# IMUinator2368_v2.net
KiCad netlist of a schematic drawn in EAGLE
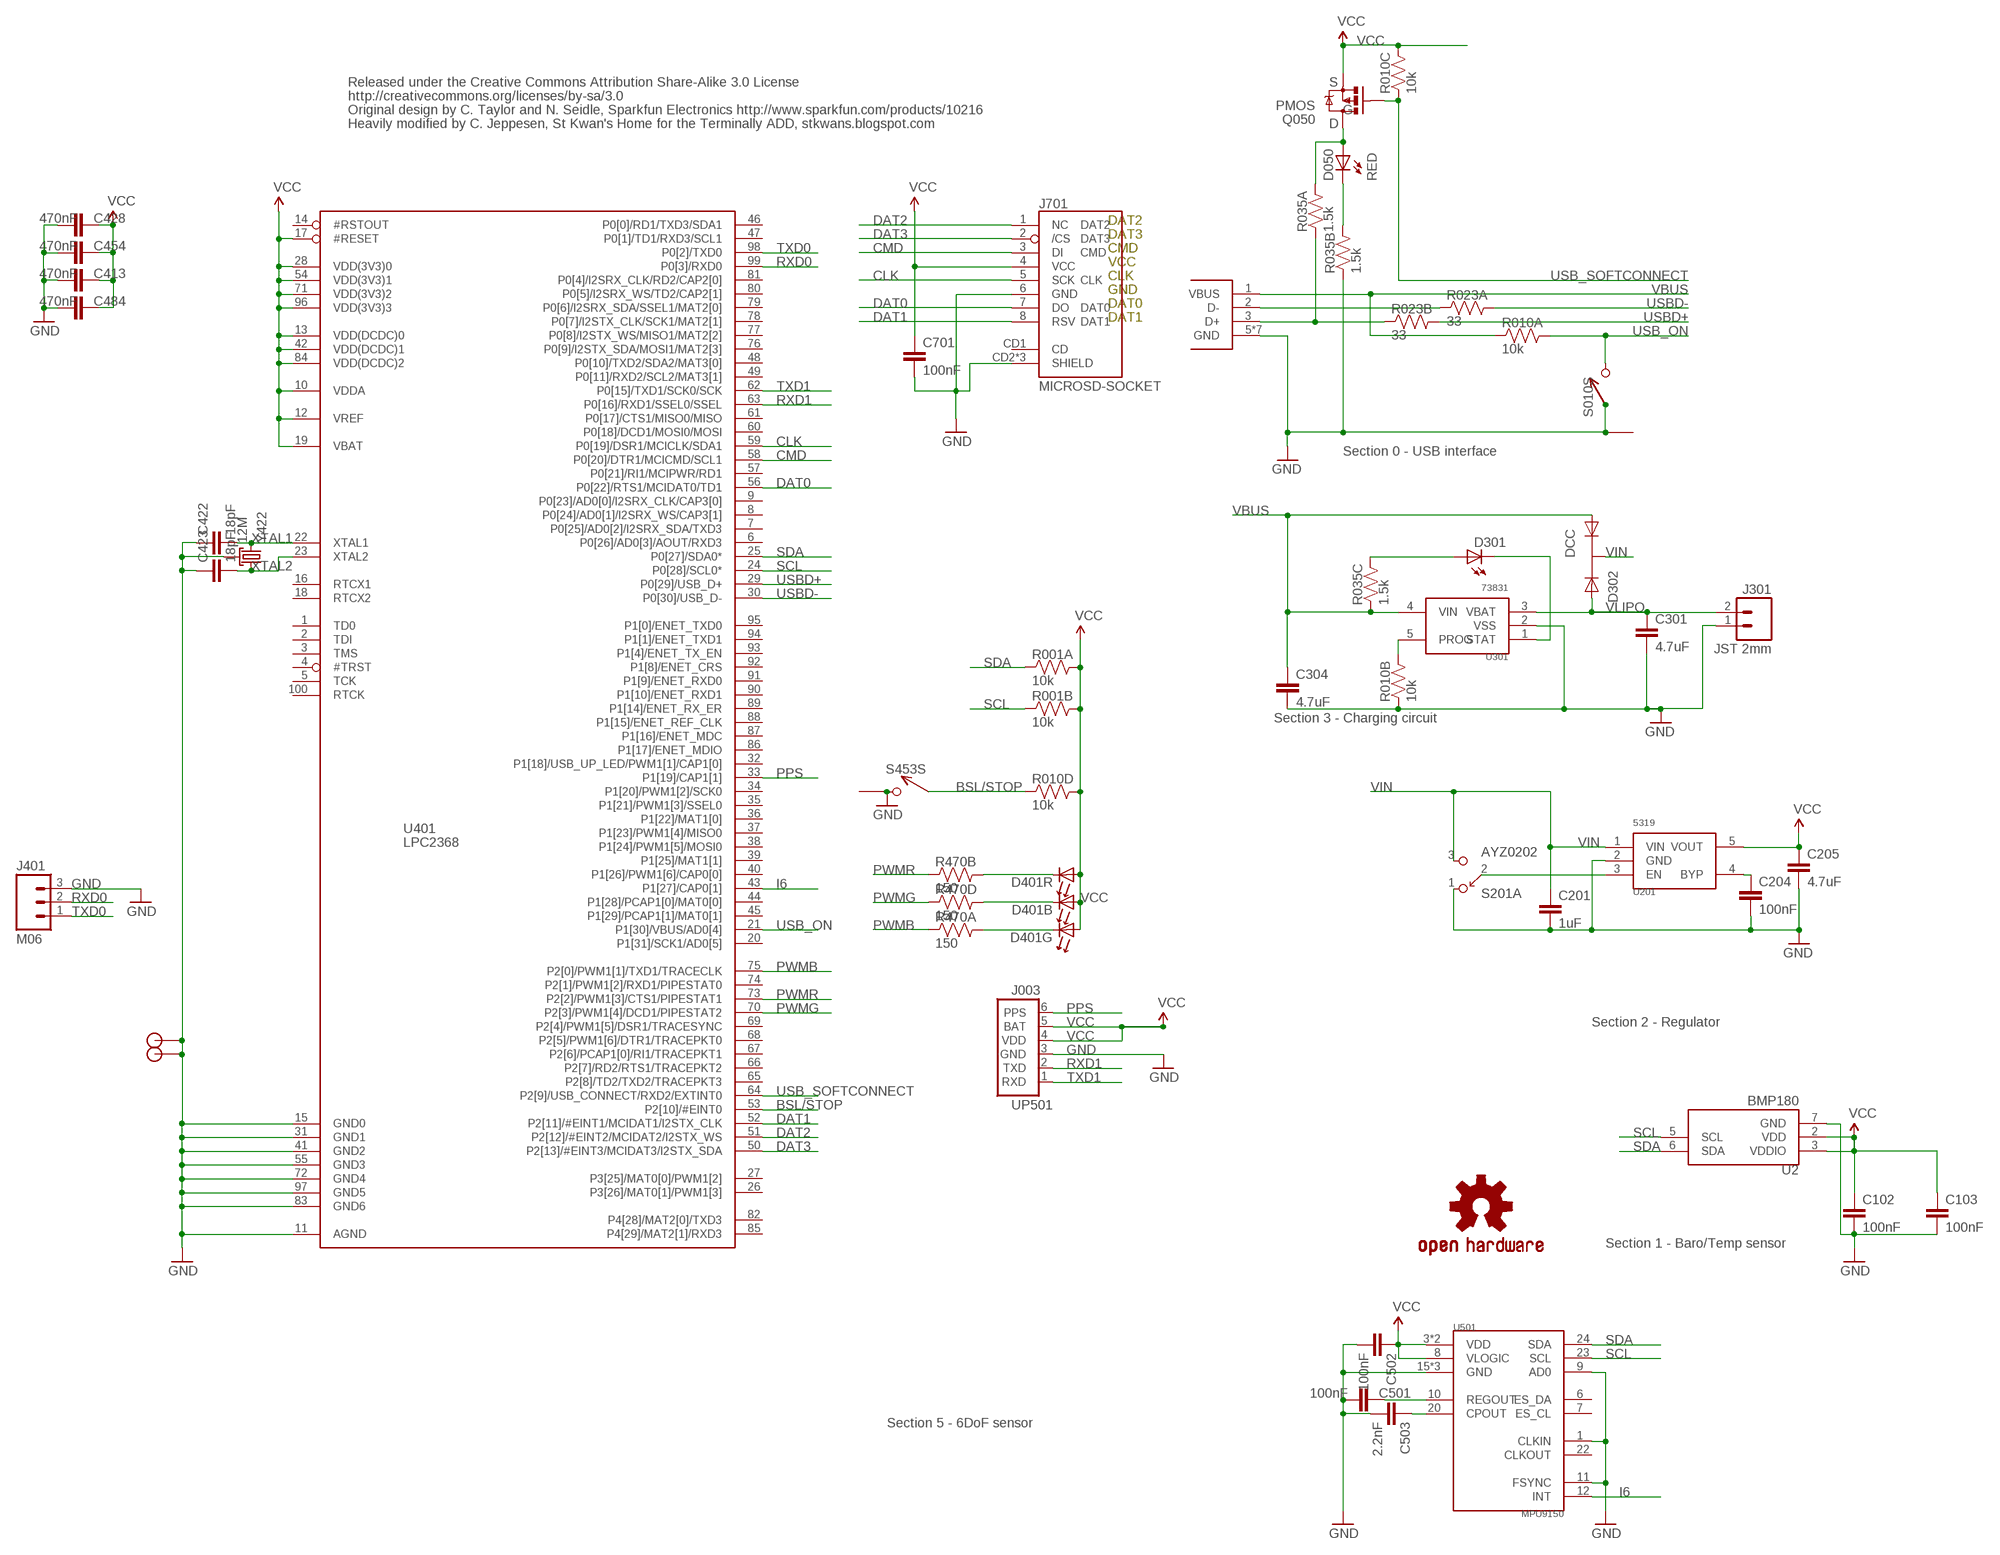
[diagram p0: schematic, sheet 1]

(export (version "E")
  (design (tool "Eeschema 10.0.6"))
  (components
    (comp (ref "C102")
      (value "100nF")
      (footprint "eagle-import:0402-CAP")
      (libsource (lib "eagle-import") (part "CAP0402-CAP"))
    )
    (comp (ref "C103")
      (value "100nF")
      (footprint "eagle-import:0402-CAP")
      (libsource (lib "eagle-import") (part "CAP0402-CAP"))
    )
    (comp (ref "C201")
      (value "1uF")
      (footprint "eagle-import:0402-CAP")
      (libsource (lib "eagle-import") (part "CAP0402-CAP"))
    )
    (comp (ref "C204")
      (value "100nF")
      (footprint "eagle-import:0402-CAP")
      (libsource (lib "eagle-import") (part "CAP0402-CAP"))
    )
    (comp (ref "C205")
      (value "4.7uF")
      (footprint "eagle-import:0402-CAP")
      (libsource (lib "eagle-import") (part "CAP0402-CAP"))
    )
    (comp (ref "C301")
      (value "4.7uF")
      (footprint "eagle-import:0402-CAP")
      (libsource (lib "eagle-import") (part "CAP0402-CAP"))
    )
    (comp (ref "C304")
      (value "4.7uF")
      (footprint "eagle-import:0402-CAP")
      (libsource (lib "eagle-import") (part "CAP0402-CAP"))
    )
    (comp (ref "C413")
      (value "470nF")
      (footprint "eagle-import:0402-CAP")
      (libsource (lib "eagle-import") (part "CAP0402-CAP"))
    )
    (comp (ref "C422")
      (value "18pF")
      (footprint "eagle-import:0402-CAP")
      (libsource (lib "eagle-import") (part "CAP0402-CAP"))
    )
    (comp (ref "C423")
      (value "18pF")
      (footprint "eagle-import:0402-CAP")
      (libsource (lib "eagle-import") (part "CAP0402-CAP"))
    )
    (comp (ref "C428")
      (value "470nF")
      (footprint "eagle-import:0402-CAP")
      (libsource (lib "eagle-import") (part "CAP0402-CAP"))
    )
    (comp (ref "C454")
      (value "470nF")
      (footprint "eagle-import:0402-CAP")
      (libsource (lib "eagle-import") (part "CAP0402-CAP"))
    )
    (comp (ref "C484")
      (value "470nF")
      (footprint "eagle-import:0402-CAP")
      (libsource (lib "eagle-import") (part "CAP0402-CAP"))
    )
    (comp (ref "C501")
      (value "100nF")
      (footprint "eagle-import:0402-CAP")
      (libsource (lib "eagle-import") (part "CAP0402-CAP"))
    )
    (comp (ref "C502")
      (value "100nF")
      (footprint "eagle-import:0402-CAP")
      (libsource (lib "eagle-import") (part "CAP0402-CAP"))
    )
    (comp (ref "C503")
      (value "2.2nF")
      (footprint "eagle-import:0402-CAP")
      (libsource (lib "eagle-import") (part "CAP0402-CAP"))
    )
    (comp (ref "C701")
      (value "100nF")
      (footprint "eagle-import:0402-CAP")
      (libsource (lib "eagle-import") (part "CAP0402-CAP"))
    )
    (comp (ref "D050")
      (value "RED")
      (footprint "eagle-import:LED-0603")
      (libsource (lib "eagle-import") (part "LED0603"))
    )
    (comp (ref "D301")
      (value "RED")
      (footprint "eagle-import:LED-0603")
      (libsource (lib "eagle-import") (part "LED0603"))
    )
    (comp (ref "D302")
      (value "DCC")
      (footprint "eagle-import:SOT-23-3")
      (libsource (lib "eagle-import") (part "PMEG2005CT"))
    )
    (comp (ref "D401")
      (value "SMLP36RGB2W(R)")
      (footprint "eagle-import:SMLP36")
      (libsource (lib "eagle-import") (part "SMLP36RGB2W(R)"))
    )
    (comp (ref "J001")
      (value "USB_MICROB_JSTGCT")
      (footprint "eagle-import:USB_MICROB_3075")
      (libsource (lib "eagle-import") (part "USB_MICROB_JSTGCT"))
    )
    (comp (ref "J003")
      (value "UP501")
      (footprint "eagle-import:UP501")
      (libsource (lib "eagle-import") (part "UP501"))
    )
    (comp (ref "J301")
      (value "JST 2mm")
      (footprint "eagle-import:JST-2-SMD")
      (libsource (lib "eagle-import") (part "M02-JST-2MM-SMT"))
    )
    (comp (ref "J401")
      (value "M06")
      (footprint "eagle-import:1X03")
      (libsource (lib "eagle-import") (part "M03PTH"))
    )
    (comp (ref "J701")
      (value "MICROSD-SOCKET")
      (footprint "eagle-import:MICROSD-SOCKET-PP")
      (libsource (lib "eagle-import") (part "MICROSD-SOCKET"))
    )
    (comp (ref "JP1")
      (value "STANDOFF")
      (footprint "eagle-import:STANDOFF")
      (libsource (lib "eagle-import") (part "STANDOFF"))
    )
    (comp (ref "JP2")
      (value "STANDOFF")
      (footprint "eagle-import:STANDOFF")
      (libsource (lib "eagle-import") (part "STANDOFF"))
    )
    (comp (ref "Q050")
      (value "PMOS")
      (footprint "eagle-import:SOT23-3")
      (libsource (lib "eagle-import") (part "MOSFET-PCHANNELSMD"))
    )
    (comp (ref "R001")
      (value "10k")
      (footprint "eagle-import:CRA02")
      (libsource (lib "eagle-import") (part "RP2EXB24V"))
    )
    (comp (ref "R010")
      (value "10k")
      (footprint "eagle-import:CRA04")
      (libsource (lib "eagle-import") (part "RP404"))
    )
    (comp (ref "R023")
      (value "33")
      (footprint "eagle-import:CRA02")
      (libsource (lib "eagle-import") (part "RP2EXB24V"))
    )
    (comp (ref "R035")
      (value "1.5k")
      (footprint "eagle-import:CRA04")
      (libsource (lib "eagle-import") (part "RP404"))
    )
    (comp (ref "R470")
      (value "150")
      (footprint "eagle-import:CRA04")
      (libsource (lib "eagle-import") (part "RP404"))
    )
    (comp (ref "S010")
      (value "SPST")
      (footprint "eagle-import:B3U-1100P")
      (fields (field (name "DIGIKEY") "SW1021CT-ND"))
      (libsource (lib "eagle-import") (part "B3U-1100P"))
    )
    (comp (ref "S201")
      (value "AYZ0202")
      (footprint "eagle-import:AYZ0202")
      (libsource (lib "eagle-import") (part "AYZ0202"))
    )
    (comp (ref "S453")
      (value "SPST")
      (footprint "eagle-import:B3U-1100P")
      (fields (field (name "DIGIKEY") "SW1021CT-ND"))
      (libsource (lib "eagle-import") (part "B3U-1100P"))
    )
    (comp (ref "U$3")
      (value "OSHW-LOGOS")
      (footprint "eagle-import:OSHW-LOGO-S")
      (libsource (lib "eagle-import") (part "OSHW-LOGOS"))
    )
    (comp (ref "U2")
      (value "BMP180")
      (footprint "eagle-import:BMP180")
      (libsource (lib "eagle-import") (part "BMP180"))
    )
    (comp (ref "U201")
      (value "5319")
      (footprint "eagle-import:SOT-23-5")
      (libsource (lib "eagle-import") (part "MIC5319D5"))
    )
    (comp (ref "U301")
      (value "73831")
      (footprint "eagle-import:SOT-23-5")
      (libsource (lib "eagle-import") (part "MCP73831"))
    )
    (comp (ref "U401")
      (value "LPC2368")
      (footprint "eagle-import:LQFP100")
      (libsource (lib "eagle-import") (part "LPC2368"))
    )
    (comp (ref "U501")
      (value "MPU9150")
      (footprint "eagle-import:LLGA24")
      (libsource (lib "eagle-import") (part "MPU9150"))
    )
    (comp (ref "Y422")
      (value "12M")
      (footprint "eagle-import:CRYSTAL_SMD_2MM_2_5MM")
      (fields (field (name "DIGIKEY") "887-1316-1-ND"))
      (libsource (lib "eagle-import") (part "CX2520"))
    )
  )
  (nets
    (net (code "1") (name "/BSL{slash}STOP") (class "Default")
      (node (ref "R010") (pin "4") (pinfunction "1_4") (pintype "passive"))
      (node (ref "S453") (pin "P$1") (pinfunction "1_P$1") (pintype "bidirectional"))
      (node (ref "U401") (pin "53") (pinfunction "P2[10]/#EINT0_53") (pintype "bidirectional"))
    )
    (net (code "2") (name "/CLK") (class "Default")
      (node (ref "J701") (pin "5") (pinfunction "SCK_5") (pintype "bidirectional"))
      (node (ref "U401") (pin "59") (pinfunction "P0[19]/DSR1/MCICLK/SDA1_59") (pintype "bidirectional"))
    )
    (net (code "3") (name "/CMD") (class "Default")
      (node (ref "J701") (pin "3") (pinfunction "DI_3") (pintype "bidirectional"))
      (node (ref "U401") (pin "58") (pinfunction "P0[20]/DTR1/MCICMD/SCL1_58") (pintype "bidirectional"))
    )
    (net (code "4") (name "/DAT0") (class "Default")
      (node (ref "J701") (pin "7") (pinfunction "DO_7") (pintype "bidirectional"))
      (node (ref "U401") (pin "56") (pinfunction "P0[22]/RTS1/MCIDAT0/TD1_56") (pintype "bidirectional"))
    )
    (net (code "5") (name "/DAT1") (class "Default")
      (node (ref "J701") (pin "8") (pinfunction "RSV_8") (pintype "bidirectional"))
      (node (ref "U401") (pin "52") (pinfunction "P2[11]/#EINT1/MCIDAT1/I2STX_CLK_52") (pintype "bidirectional"))
    )
    (net (code "6") (name "/DAT2") (class "Default")
      (node (ref "J701") (pin "1") (pinfunction "NC_1") (pintype "bidirectional"))
      (node (ref "U401") (pin "51") (pinfunction "P2[12]/#EINT2/MCIDAT2/I2STX_WS_51") (pintype "bidirectional"))
    )
    (net (code "7") (name "/DAT3") (class "Default")
      (node (ref "J701") (pin "2") (pinfunction "/CS_2") (pintype "bidirectional"))
      (node (ref "U401") (pin "50") (pinfunction "P2[13]/#EINT3/MCIDAT3/I2STX_SDA_50") (pintype "bidirectional"))
    )
    (net (code "8") (name "/I6") (class "Default")
      (node (ref "U401") (pin "43") (pinfunction "P1[27]/CAP0[1]_43") (pintype "bidirectional"))
      (node (ref "U501") (pin "12") (pinfunction "INT_12") (pintype "bidirectional"))
    )
    (net (code "9") (name "/PPS") (class "Default")
      (node (ref "J003") (pin "6") (pinfunction "PPS_6") (pintype "passive"))
      (node (ref "U401") (pin "33") (pinfunction "P1[19]/CAP1[1]_33") (pintype "bidirectional"))
    )
    (net (code "10") (name "/PWMB") (class "Default")
      (node (ref "R470") (pin "1") (pinfunction "1_1") (pintype "passive"))
      (node (ref "U401") (pin "75") (pinfunction "P2[0]/PWM1[1]/TXD1/TRACECLK_75") (pintype "bidirectional"))
    )
    (net (code "11") (name "/PWMG") (class "Default")
      (node (ref "R470") (pin "4") (pinfunction "1_4") (pintype "passive"))
      (node (ref "U401") (pin "70") (pinfunction "P2[3]/PWM1[4]/DCD1/PIPESTAT2_70") (pintype "bidirectional"))
    )
    (net (code "12") (name "/PWMR") (class "Default")
      (node (ref "R470") (pin "2") (pinfunction "1_2") (pintype "passive"))
      (node (ref "U401") (pin "73") (pinfunction "P2[2]/PWM1[3]/CTS1/PIPESTAT1_73") (pintype "bidirectional"))
    )
    (net (code "13") (name "/RXD0") (class "Default")
      (node (ref "J401") (pin "2") (pinfunction "2_2") (pintype "passive"))
      (node (ref "U401") (pin "99") (pinfunction "P0[3]/RXD0_99") (pintype "bidirectional"))
    )
    (net (code "14") (name "/RXD1") (class "Default")
      (node (ref "J003") (pin "2") (pinfunction "TXD_2") (pintype "passive"))
      (node (ref "U401") (pin "63") (pinfunction "P0[16]/RXD1/SSEL0/SSEL_63") (pintype "bidirectional"))
    )
    (net (code "15") (name "/SCL") (class "Default")
      (node (ref "R001") (pin "2") (pinfunction "1_2") (pintype "passive"))
      (node (ref "U2") (pin "5") (pinfunction "SCL_5") (pintype "input"))
      (node (ref "U401") (pin "24") (pinfunction "P0[28]/SCL0*_24") (pintype "bidirectional"))
      (node (ref "U501") (pin "23") (pinfunction "SCL_23") (pintype "bidirectional"))
    )
    (net (code "16") (name "/SDA") (class "Default")
      (node (ref "R001") (pin "1") (pinfunction "1_1") (pintype "passive"))
      (node (ref "U2") (pin "6") (pinfunction "SDA_6") (pintype "bidirectional"))
      (node (ref "U401") (pin "25") (pinfunction "P0[27]/SDA0*_25") (pintype "bidirectional"))
      (node (ref "U501") (pin "24") (pinfunction "SDA_24") (pintype "bidirectional"))
    )
    (net (code "17") (name "/TXD0") (class "Default")
      (node (ref "J401") (pin "1") (pinfunction "1_1") (pintype "passive"))
      (node (ref "U401") (pin "98") (pinfunction "P0[2]/TXD0_98") (pintype "bidirectional"))
    )
    (net (code "18") (name "/TXD1") (class "Default")
      (node (ref "J003") (pin "1") (pinfunction "RXD_1") (pintype "passive"))
      (node (ref "U401") (pin "62") (pinfunction "P0[15]/TXD1/SCK0/SCK_62") (pintype "bidirectional"))
    )
    (net (code "19") (name "/USBD+") (class "Default")
      (node (ref "R023") (pin "3") (pinfunction "2_3") (pintype "passive"))
      (node (ref "U401") (pin "29") (pinfunction "P0[29]/USB_D+_29") (pintype "bidirectional"))
    )
    (net (code "20") (name "/USBD-") (class "Default")
      (node (ref "R023") (pin "4") (pinfunction "2_4") (pintype "passive"))
      (node (ref "U401") (pin "30") (pinfunction "P0[30]/USB_D-_30") (pintype "bidirectional"))
    )
    (net (code "21") (name "/USB_ON") (class "Default")
      (node (ref "R010") (pin "8") (pinfunction "2_8") (pintype "passive"))
      (node (ref "S010") (pin "P$2") (pinfunction "2_P$2") (pintype "bidirectional"))
      (node (ref "U401") (pin "21") (pinfunction "P1[30]/VBUS/AD0[4]_21") (pintype "bidirectional"))
    )
    (net (code "22") (name "/USB_SOFTCONNECT") (class "Default")
      (node (ref "Q050") (pin "1") (pinfunction "G_1") (pintype "passive"))
      (node (ref "R010") (pin "3") (pinfunction "1_3") (pintype "passive"))
      (node (ref "U401") (pin "64") (pinfunction "P2[9]/USB_CONNECT/RXD2/EXTINT0_64") (pintype "bidirectional"))
    )
    (net (code "23") (name "/VBUS") (class "Default")
      (node (ref "C304") (pin "1") (pinfunction "1_1") (pintype "passive"))
      (node (ref "D302") (pin "1") (pinfunction "A1_1") (pintype "passive"))
      (node (ref "J001") (pin "1") (pinfunction "VBUS_1") (pintype "bidirectional"))
      (node (ref "R010") (pin "1") (pinfunction "1_1") (pintype "passive"))
      (node (ref "R035") (pin "3") (pinfunction "1_3") (pintype "passive"))
      (node (ref "U301") (pin "4") (pinfunction "VIN_4") (pintype "power_in"))
    )
    (net (code "24") (name "/VIN") (class "Default")
      (node (ref "C201") (pin "1") (pinfunction "1_1") (pintype "passive"))
      (node (ref "D302") (pin "3") (pinfunction "K_3") (pintype "passive"))
      (node (ref "S201") (pin "3") (pinfunction "P$2_3") (pintype "bidirectional"))
      (node (ref "U201") (pin "1") (pinfunction "VIN_1") (pintype "bidirectional"))
    )
    (net (code "25") (name "/VLIPO") (class "Default")
      (node (ref "C301") (pin "1") (pinfunction "1_1") (pintype "passive"))
      (node (ref "D302") (pin "2") (pinfunction "A2_2") (pintype "passive"))
      (node (ref "J301") (pin "2") (pinfunction "2_2") (pintype "passive"))
      (node (ref "U301") (pin "3") (pinfunction "VBAT_3") (pintype "power_in"))
    )
    (net (code "26") (name "/XTAL1") (class "Default")
      (node (ref "C422") (pin "2") (pinfunction "2_2") (pintype "passive"))
      (node (ref "U401") (pin "22") (pinfunction "XTAL1_22") (pintype "bidirectional"))
      (node (ref "Y422") (pin "3") (pinfunction "2_3") (pintype "passive"))
    )
    (net (code "27") (name "/XTAL2") (class "Default")
      (node (ref "C423") (pin "2") (pinfunction "2_2") (pintype "passive"))
      (node (ref "U401") (pin "23") (pinfunction "XTAL2_23") (pintype "bidirectional"))
      (node (ref "Y422") (pin "1") (pinfunction "1_1") (pintype "passive"))
    )
    (net (code "28") (name "GND") (class "Default")
      (node (ref "C102") (pin "2") (pinfunction "2_2") (pintype "passive"))
      (node (ref "C103") (pin "2") (pinfunction "2_2") (pintype "passive"))
      (node (ref "C201") (pin "2") (pinfunction "2_2") (pintype "passive"))
      (node (ref "C204") (pin "2") (pinfunction "2_2") (pintype "passive"))
      (node (ref "C205") (pin "2") (pinfunction "2_2") (pintype "passive"))
      (node (ref "C301") (pin "2") (pinfunction "2_2") (pintype "passive"))
      (node (ref "C304") (pin "2") (pinfunction "2_2") (pintype "passive"))
      (node (ref "C413") (pin "2") (pinfunction "2_2") (pintype "passive"))
      (node (ref "C422") (pin "1") (pinfunction "1_1") (pintype "passive"))
      (node (ref "C423") (pin "1") (pinfunction "1_1") (pintype "passive"))
      (node (ref "C428") (pin "2") (pinfunction "2_2") (pintype "passive"))
      (node (ref "C454") (pin "2") (pinfunction "2_2") (pintype "passive"))
      (node (ref "C484") (pin "2") (pinfunction "2_2") (pintype "passive"))
      (node (ref "C501") (pin "2") (pinfunction "2_2") (pintype "passive"))
      (node (ref "C502") (pin "2") (pinfunction "2_2") (pintype "passive"))
      (node (ref "C503") (pin "2") (pinfunction "2_2") (pintype "passive"))
      (node (ref "C701") (pin "2") (pinfunction "2_2") (pintype "passive"))
      (node (ref "J001") (pin "5") (pinfunction "GND_5") (pintype "bidirectional"))
      (node (ref "J001") (pin "P$1") (pinfunction "GND_P$1") (pintype "bidirectional"))
      (node (ref "J001") (pin "P$10") (pinfunction "GND_P$10") (pintype "bidirectional"))
      (node (ref "J001") (pin "P$2") (pinfunction "GND_P$2") (pintype "bidirectional"))
      (node (ref "J001") (pin "P$3") (pinfunction "GND_P$3") (pintype "bidirectional"))
      (node (ref "J001") (pin "P$4") (pinfunction "GND_P$4") (pintype "bidirectional"))
      (node (ref "J001") (pin "P$8") (pinfunction "GND_P$8") (pintype "bidirectional"))
      (node (ref "J003") (pin "3") (pinfunction "GND_3") (pintype "passive"))
      (node (ref "J301") (pin "1") (pinfunction "1_1") (pintype "passive"))
      (node (ref "J401") (pin "3") (pinfunction "3_3") (pintype "passive"))
      (node (ref "J701") (pin "6") (pinfunction "GND_6") (pintype "bidirectional"))
      (node (ref "J701") (pin "CD2") (pinfunction "SHIELD_CD2") (pintype "bidirectional"))
      (node (ref "J701") (pin "GND1") (pinfunction "SHIELD_GND1") (pintype "bidirectional"))
      (node (ref "J701") (pin "GND3") (pinfunction "SHIELD_GND3") (pintype "bidirectional"))
      (node (ref "JP1") (pin "P$1") (pinfunction "P$1_P$1") (pintype "bidirectional"))
      (node (ref "JP2") (pin "P$1") (pinfunction "P$1_P$1") (pintype "bidirectional"))
      (node (ref "R010") (pin "2") (pinfunction "1_2") (pintype "passive"))
      (node (ref "R035") (pin "2") (pinfunction "1_2") (pintype "passive"))
      (node (ref "S010") (pin "P$1") (pinfunction "1_P$1") (pintype "bidirectional"))
      (node (ref "S010") (pin "P$3") (pinfunction "1_P$3") (pintype "bidirectional"))
      (node (ref "S201") (pin "1") (pinfunction "P$1_1") (pintype "bidirectional"))
      (node (ref "S453") (pin "P$2") (pinfunction "2_P$2") (pintype "bidirectional"))
      (node (ref "S453") (pin "P$3") (pinfunction "1_P$3") (pintype "bidirectional"))
      (node (ref "U2") (pin "7") (pinfunction "GND_7") (pintype "power_in"))
      (node (ref "U201") (pin "2") (pinfunction "GND_2") (pintype "bidirectional"))
      (node (ref "U301") (pin "2") (pinfunction "VSS_2") (pintype "power_in"))
      (node (ref "U401") (pin "11") (pinfunction "AGND_11") (pintype "bidirectional"))
      (node (ref "U401") (pin "15") (pinfunction "GND0_15") (pintype "bidirectional"))
      (node (ref "U401") (pin "31") (pinfunction "GND1_31") (pintype "bidirectional"))
      (node (ref "U401") (pin "41") (pinfunction "GND2_41") (pintype "bidirectional"))
      (node (ref "U401") (pin "55") (pinfunction "GND3_55") (pintype "bidirectional"))
      (node (ref "U401") (pin "72") (pinfunction "GND4_72") (pintype "bidirectional"))
      (node (ref "U401") (pin "83") (pinfunction "GND6_83") (pintype "bidirectional"))
      (node (ref "U401") (pin "97") (pinfunction "GND5_97") (pintype "bidirectional"))
      (node (ref "U501") (pin "1") (pinfunction "CLKIN_1") (pintype "bidirectional"))
      (node (ref "U501") (pin "11") (pinfunction "FSYNC_11") (pintype "bidirectional"))
      (node (ref "U501") (pin "15") (pinfunction "GND_15") (pintype "bidirectional"))
      (node (ref "U501") (pin "17") (pinfunction "GND_17") (pintype "bidirectional"))
      (node (ref "U501") (pin "18") (pinfunction "GND_18") (pintype "bidirectional"))
      (node (ref "U501") (pin "9") (pinfunction "AD0_9") (pintype "bidirectional"))
      (node (ref "Y422") (pin "2") (pinfunction "GND_2") (pintype "passive"))
      (node (ref "Y422") (pin "4") (pinfunction "GND_4") (pintype "passive"))
    )
    (net (code "29") (name "Net-(D401A-C)") (class "Default")
      (node (ref "D401") (pin "1") (pinfunction "C_1") (pintype "passive"))
      (node (ref "R470") (pin "5") (pinfunction "2_5") (pintype "passive"))
    )
    (net (code "30") (name "Net-(D401B-C)") (class "Default")
      (node (ref "D401") (pin "5") (pinfunction "C_5") (pintype "passive"))
      (node (ref "R470") (pin "8") (pinfunction "2_8") (pintype "passive"))
    )
    (net (code "31") (name "Net-(D401C-C)") (class "Default")
      (node (ref "D401") (pin "3") (pinfunction "C_3") (pintype "passive"))
      (node (ref "R470") (pin "7") (pinfunction "2_7") (pintype "passive"))
    )
    (net (code "32") (name "Net-(J001-D+)") (class "Default")
      (node (ref "J001") (pin "3") (pinfunction "D+_3") (pintype "bidirectional"))
      (node (ref "R023") (pin "2") (pinfunction "1_2") (pintype "passive"))
      (node (ref "R035") (pin "1") (pinfunction "1_1") (pintype "passive"))
    )
    (net (code "33") (name "Net-(J001-D-)") (class "Default")
      (node (ref "J001") (pin "2") (pinfunction "D-_2") (pintype "bidirectional"))
      (node (ref "R023") (pin "1") (pinfunction "1_1") (pintype "passive"))
    )
    (net (code "34") (name "Net-(Q050-D)") (class "Default")
      (node (ref "D050") (pin "A") (pinfunction "A_A") (pintype "passive"))
      (node (ref "Q050") (pin "3") (pinfunction "D_3") (pintype "passive"))
      (node (ref "R035") (pin "8") (pinfunction "2_8") (pintype "passive"))
    )
    (net (code "35") (name "Net-(R010B-2)") (class "Default")
      (node (ref "R010") (pin "7") (pinfunction "2_7") (pintype "passive"))
      (node (ref "U301") (pin "5") (pinfunction "PROG_5") (pintype "passive"))
    )
    (net (code "36") (name "Net-(R035B-2)") (class "Default")
      (node (ref "D050") (pin "C") (pinfunction "C_C") (pintype "passive"))
      (node (ref "R035") (pin "7") (pinfunction "2_7") (pintype "passive"))
    )
    (net (code "37") (name "Net-(R035C-2)") (class "Default")
      (node (ref "D301") (pin "A") (pinfunction "A_A") (pintype "passive"))
      (node (ref "R035") (pin "6") (pinfunction "2_6") (pintype "passive"))
    )
    (net (code "38") (name "Net-(S201A-P$3)") (class "Default")
      (node (ref "S201") (pin "2") (pinfunction "P$3_2") (pintype "bidirectional"))
      (node (ref "U201") (pin "3") (pinfunction "EN_3") (pintype "bidirectional"))
    )
    (net (code "39") (name "Net-(U201-BYP)") (class "Default")
      (node (ref "C204") (pin "1") (pinfunction "1_1") (pintype "passive"))
      (node (ref "U201") (pin "4") (pinfunction "BYP_4") (pintype "bidirectional"))
    )
    (net (code "40") (name "Net-(U301-STAT)") (class "Default")
      (node (ref "D301") (pin "C") (pinfunction "C_C") (pintype "passive"))
      (node (ref "U301") (pin "1") (pinfunction "STAT_1") (pintype "bidirectional"))
    )
    (net (code "41") (name "Net-(U501-CPOUT)") (class "Default")
      (node (ref "C503") (pin "1") (pinfunction "1_1") (pintype "passive"))
      (node (ref "U501") (pin "20") (pinfunction "CPOUT_20") (pintype "bidirectional"))
    )
    (net (code "42") (name "Net-(U501-REGOUT)") (class "Default")
      (node (ref "C501") (pin "1") (pinfunction "1_1") (pintype "passive"))
      (node (ref "U501") (pin "10") (pinfunction "REGOUT_10") (pintype "bidirectional"))
    )
    (net (code "43") (name "VCC") (class "Default")
      (node (ref "C102") (pin "1") (pinfunction "1_1") (pintype "passive"))
      (node (ref "C103") (pin "1") (pinfunction "1_1") (pintype "passive"))
      (node (ref "C205") (pin "1") (pinfunction "1_1") (pintype "passive"))
      (node (ref "C413") (pin "1") (pinfunction "1_1") (pintype "passive"))
      (node (ref "C428") (pin "1") (pinfunction "1_1") (pintype "passive"))
      (node (ref "C454") (pin "1") (pinfunction "1_1") (pintype "passive"))
      (node (ref "C484") (pin "1") (pinfunction "1_1") (pintype "passive"))
      (node (ref "C502") (pin "1") (pinfunction "1_1") (pintype "passive"))
      (node (ref "C701") (pin "1") (pinfunction "1_1") (pintype "passive"))
      (node (ref "D401") (pin "2") (pinfunction "A_2") (pintype "passive"))
      (node (ref "D401") (pin "4") (pinfunction "A_4") (pintype "passive"))
      (node (ref "D401") (pin "6") (pinfunction "A_6") (pintype "passive"))
      (node (ref "J003") (pin "4") (pinfunction "VDD_4") (pintype "passive"))
      (node (ref "J003") (pin "5") (pinfunction "BAT_5") (pintype "passive"))
      (node (ref "J701") (pin "4") (pinfunction "VCC_4") (pintype "bidirectional"))
      (node (ref "Q050") (pin "2") (pinfunction "S_2") (pintype "passive"))
      (node (ref "R001") (pin "3") (pinfunction "2_3") (pintype "passive"))
      (node (ref "R001") (pin "4") (pinfunction "2_4") (pintype "passive"))
      (node (ref "R010") (pin "5") (pinfunction "2_5") (pintype "passive"))
      (node (ref "R010") (pin "6") (pinfunction "2_6") (pintype "passive"))
      (node (ref "U2") (pin "2") (pinfunction "VDD_2") (pintype "power_in"))
      (node (ref "U2") (pin "3") (pinfunction "VDDIO_3") (pintype "power_in"))
      (node (ref "U201") (pin "5") (pinfunction "VOUT_5") (pintype "bidirectional"))
      (node (ref "U401") (pin "10") (pinfunction "VDDA_10") (pintype "bidirectional"))
      (node (ref "U401") (pin "12") (pinfunction "VREF_12") (pintype "bidirectional"))
      (node (ref "U401") (pin "13") (pinfunction "VDD(DCDC)0_13") (pintype "bidirectional"))
      (node (ref "U401") (pin "17") (pinfunction "#RESET_17") (pintype "bidirectional"))
      (node (ref "U401") (pin "19") (pinfunction "VBAT_19") (pintype "bidirectional"))
      (node (ref "U401") (pin "28") (pinfunction "VDD(3V3)0_28") (pintype "bidirectional"))
      (node (ref "U401") (pin "42") (pinfunction "VDD(DCDC)1_42") (pintype "bidirectional"))
      (node (ref "U401") (pin "54") (pinfunction "VDD(3V3)1_54") (pintype "bidirectional"))
      (node (ref "U401") (pin "71") (pinfunction "VDD(3V3)2_71") (pintype "bidirectional"))
      (node (ref "U401") (pin "84") (pinfunction "VDD(DCDC)2_84") (pintype "bidirectional"))
      (node (ref "U401") (pin "96") (pinfunction "VDD(3V3)3_96") (pintype "bidirectional"))
      (node (ref "U501") (pin "13") (pinfunction "VDD_13") (pintype "bidirectional"))
      (node (ref "U501") (pin "3") (pinfunction "VDD_3") (pintype "bidirectional"))
      (node (ref "U501") (pin "8") (pinfunction "VLOGIC_8") (pintype "bidirectional"))
    )
    (net (code "44") (name "unconnected-(J701-CD-PadCD1)") (class "Default")
      (node (ref "J701") (pin "CD1") (pinfunction "CD_CD1") (pintype "bidirectional"))
    )
    (net (code "45") (name "unconnected-(U401-#RSTOUT-Pad14)") (class "Default")
      (node (ref "U401") (pin "14") (pinfunction "#RSTOUT_14") (pintype "bidirectional"))
    )
    (net (code "46") (name "unconnected-(U401-#TRST-Pad4)") (class "Default")
      (node (ref "U401") (pin "4") (pinfunction "#TRST_4") (pintype "bidirectional"))
    )
    (net (code "47") (name "unconnected-(U401-P0[0]{slash}RD1{slash}TXD3{slash}SDA1-Pad46)") (class "Default")
      (node (ref "U401") (pin "46") (pinfunction "P0[0]/RD1/TXD3/SDA1_46") (pintype "bidirectional"))
    )
    (net (code "48") (name "unconnected-(U401-P0[1]{slash}TD1{slash}RXD3{slash}SCL1-Pad47)") (class "Default")
      (node (ref "U401") (pin "47") (pinfunction "P0[1]/TD1/RXD3/SCL1_47") (pintype "bidirectional"))
    )
    (net (code "49") (name "unconnected-(U401-P0[4]{slash}I2SRX_CLK{slash}RD2{slash}CAP2[0]-Pad81)") (class "Default")
      (node (ref "U401") (pin "81") (pinfunction "P0[4]/I2SRX_CLK/RD2/CAP2[0]_81") (pintype "bidirectional"))
    )
    (net (code "50") (name "unconnected-(U401-P0[5]{slash}I2SRX_WS{slash}TD2{slash}CAP2[1]-Pad80)") (class "Default")
      (node (ref "U401") (pin "80") (pinfunction "P0[5]/I2SRX_WS/TD2/CAP2[1]_80") (pintype "bidirectional"))
    )
    (net (code "51") (name "unconnected-(U401-P0[6]{slash}I2SRX_SDA{slash}SSEL1{slash}MAT2[0]-Pad79)") (class "Default")
      (node (ref "U401") (pin "79") (pinfunction "P0[6]/I2SRX_SDA/SSEL1/MAT2[0]_79") (pintype "bidirectional"))
    )
    (net (code "52") (name "unconnected-(U401-P0[7]{slash}I2STX_CLK{slash}SCK1{slash}MAT2[1]-Pad78)") (class "Default")
      (node (ref "U401") (pin "78") (pinfunction "P0[7]/I2STX_CLK/SCK1/MAT2[1]_78") (pintype "bidirectional"))
    )
    (net (code "53") (name "unconnected-(U401-P0[8]{slash}I2STX_WS{slash}MISO1{slash}MAT2[2]-Pad77)") (class "Default")
      (node (ref "U401") (pin "77") (pinfunction "P0[8]/I2STX_WS/MISO1/MAT2[2]_77") (pintype "bidirectional"))
    )
    (net (code "54") (name "unconnected-(U401-P0[9]{slash}I2STX_SDA{slash}MOSI1{slash}MAT2[3]-Pad76)") (class "Default")
      (node (ref "U401") (pin "76") (pinfunction "P0[9]/I2STX_SDA/MOSI1/MAT2[3]_76") (pintype "bidirectional"))
    )
    (net (code "55") (name "unconnected-(U401-P0[10]{slash}TXD2{slash}SDA2{slash}MAT3[0]-Pad48)") (class "Default")
      (node (ref "U401") (pin "48") (pinfunction "P0[10]/TXD2/SDA2/MAT3[0]_48") (pintype "bidirectional"))
    )
    (net (code "56") (name "unconnected-(U401-P0[11]{slash}RXD2{slash}SCL2{slash}MAT3[1]-Pad49)") (class "Default")
      (node (ref "U401") (pin "49") (pinfunction "P0[11]/RXD2/SCL2/MAT3[1]_49") (pintype "bidirectional"))
    )
    (net (code "57") (name "unconnected-(U401-P0[17]{slash}CTS1{slash}MISO0{slash}MISO-Pad61)") (class "Default")
      (node (ref "U401") (pin "61") (pinfunction "P0[17]/CTS1/MISO0/MISO_61") (pintype "bidirectional"))
    )
    (net (code "58") (name "unconnected-(U401-P0[18]{slash}DCD1{slash}MOSI0{slash}MOSI-Pad60)") (class "Default")
      (node (ref "U401") (pin "60") (pinfunction "P0[18]/DCD1/MOSI0/MOSI_60") (pintype "bidirectional"))
    )
    (net (code "59") (name "unconnected-(U401-P0[21]{slash}RI1{slash}MCIPWR{slash}RD1-Pad57)") (class "Default")
      (node (ref "U401") (pin "57") (pinfunction "P0[21]/RI1/MCIPWR/RD1_57") (pintype "bidirectional"))
    )
    (net (code "60") (name "unconnected-(U401-P0[23]{slash}AD0[0]{slash}I2SRX_CLK{slash}CAP3[0]-Pad9)") (class "Default")
      (node (ref "U401") (pin "9") (pinfunction "P0[23]/AD0[0]/I2SRX_CLK/CAP3[0]_9") (pintype "bidirectional"))
    )
    (net (code "61") (name "unconnected-(U401-P0[24]{slash}AD0[1]{slash}I2SRX_WS{slash}CAP3[1]-Pad8)") (class "Default")
      (node (ref "U401") (pin "8") (pinfunction "P0[24]/AD0[1]/I2SRX_WS/CAP3[1]_8") (pintype "bidirectional"))
    )
    (net (code "62") (name "unconnected-(U401-P0[25]{slash}AD0[2]{slash}I2SRX_SDA{slash}TXD3-Pad7)") (class "Default")
      (node (ref "U401") (pin "7") (pinfunction "P0[25]/AD0[2]/I2SRX_SDA/TXD3_7") (pintype "bidirectional"))
    )
    (net (code "63") (name "unconnected-(U401-P0[26]{slash}AD0[3]{slash}AOUT{slash}RXD3-Pad6)") (class "Default")
      (node (ref "U401") (pin "6") (pinfunction "P0[26]/AD0[3]/AOUT/RXD3_6") (pintype "bidirectional"))
    )
    (net (code "64") (name "unconnected-(U401-P1[0]{slash}ENET_TXD0-Pad95)") (class "Default")
      (node (ref "U401") (pin "95") (pinfunction "P1[0]/ENET_TXD0_95") (pintype "bidirectional"))
    )
    (net (code "65") (name "unconnected-(U401-P1[1]{slash}ENET_TXD1-Pad94)") (class "Default")
      (node (ref "U401") (pin "94") (pinfunction "P1[1]/ENET_TXD1_94") (pintype "bidirectional"))
    )
    (net (code "66") (name "unconnected-(U401-P1[4]{slash}ENET_TX_EN-Pad93)") (class "Default")
      (node (ref "U401") (pin "93") (pinfunction "P1[4]/ENET_TX_EN_93") (pintype "bidirectional"))
    )
    (net (code "67") (name "unconnected-(U401-P1[8]{slash}ENET_CRS-Pad92)") (class "Default")
      (node (ref "U401") (pin "92") (pinfunction "P1[8]/ENET_CRS_92") (pintype "bidirectional"))
    )
    (net (code "68") (name "unconnected-(U401-P1[9]{slash}ENET_RXD0-Pad91)") (class "Default")
      (node (ref "U401") (pin "91") (pinfunction "P1[9]/ENET_RXD0_91") (pintype "bidirectional"))
    )
    (net (code "69") (name "unconnected-(U401-P1[10]{slash}ENET_RXD1-Pad90)") (class "Default")
      (node (ref "U401") (pin "90") (pinfunction "P1[10]/ENET_RXD1_90") (pintype "bidirectional"))
    )
    (net (code "70") (name "unconnected-(U401-P1[14]{slash}ENET_RX_ER-Pad89)") (class "Default")
      (node (ref "U401") (pin "89") (pinfunction "P1[14]/ENET_RX_ER_89") (pintype "bidirectional"))
    )
    (net (code "71") (name "unconnected-(U401-P1[15]{slash}ENET_REF_CLK-Pad88)") (class "Default")
      (node (ref "U401") (pin "88") (pinfunction "P1[15]/ENET_REF_CLK_88") (pintype "bidirectional"))
    )
    (net (code "72") (name "unconnected-(U401-P1[16]{slash}ENET_MDC-Pad87)") (class "Default")
      (node (ref "U401") (pin "87") (pinfunction "P1[16]/ENET_MDC_87") (pintype "bidirectional"))
    )
    (net (code "73") (name "unconnected-(U401-P1[17]{slash}ENET_MDIO-Pad86)") (class "Default")
      (node (ref "U401") (pin "86") (pinfunction "P1[17]/ENET_MDIO_86") (pintype "bidirectional"))
    )
    (net (code "74") (name "unconnected-(U401-P1[18]{slash}USB_UP_LED{slash}PWM1[1]{slash}CAP1[0]-Pad32)") (class "Default")
      (node (ref "U401") (pin "32") (pinfunction "P1[18]/USB_UP_LED/PWM1[1]/CAP1[0]_32") (pintype "bidirectional"))
    )
    (net (code "75") (name "unconnected-(U401-P1[20]{slash}PWM1[2]{slash}SCK0-Pad34)") (class "Default")
      (node (ref "U401") (pin "34") (pinfunction "P1[20]/PWM1[2]/SCK0_34") (pintype "bidirectional"))
    )
    (net (code "76") (name "unconnected-(U401-P1[21]{slash}PWM1[3]{slash}SSEL0-Pad35)") (class "Default")
      (node (ref "U401") (pin "35") (pinfunction "P1[21]/PWM1[3]/SSEL0_35") (pintype "bidirectional"))
    )
    (net (code "77") (name "unconnected-(U401-P1[22]{slash}MAT1[0]-Pad36)") (class "Default")
      (node (ref "U401") (pin "36") (pinfunction "P1[22]/MAT1[0]_36") (pintype "bidirectional"))
    )
    (net (code "78") (name "unconnected-(U401-P1[23]{slash}PWM1[4]{slash}MISO0-Pad37)") (class "Default")
      (node (ref "U401") (pin "37") (pinfunction "P1[23]/PWM1[4]/MISO0_37") (pintype "bidirectional"))
    )
    (net (code "79") (name "unconnected-(U401-P1[24]{slash}PWM1[5]{slash}MOSI0-Pad38)") (class "Default")
      (node (ref "U401") (pin "38") (pinfunction "P1[24]/PWM1[5]/MOSI0_38") (pintype "bidirectional"))
    )
    (net (code "80") (name "unconnected-(U401-P1[25]{slash}MAT1[1]-Pad39)") (class "Default")
      (node (ref "U401") (pin "39") (pinfunction "P1[25]/MAT1[1]_39") (pintype "bidirectional"))
    )
    (net (code "81") (name "unconnected-(U401-P1[26]{slash}PWM1[6]{slash}CAP0[0]-Pad40)") (class "Default")
      (node (ref "U401") (pin "40") (pinfunction "P1[26]/PWM1[6]/CAP0[0]_40") (pintype "bidirectional"))
    )
    (net (code "82") (name "unconnected-(U401-P1[28]{slash}PCAP1[0]{slash}MAT0[0]-Pad44)") (class "Default")
      (node (ref "U401") (pin "44") (pinfunction "P1[28]/PCAP1[0]/MAT0[0]_44") (pintype "bidirectional"))
    )
    (net (code "83") (name "unconnected-(U401-P1[29]{slash}PCAP1[1]{slash}MAT0[1]-Pad45)") (class "Default")
      (node (ref "U401") (pin "45") (pinfunction "P1[29]/PCAP1[1]/MAT0[1]_45") (pintype "bidirectional"))
    )
    (net (code "84") (name "unconnected-(U401-P1[31]{slash}SCK1{slash}AD0[5]-Pad20)") (class "Default")
      (node (ref "U401") (pin "20") (pinfunction "P1[31]/SCK1/AD0[5]_20") (pintype "bidirectional"))
    )
    (net (code "85") (name "unconnected-(U401-P2[1]{slash}PWM1[2]{slash}RXD1{slash}PIPESTAT0-Pad74)") (class "Default")
      (node (ref "U401") (pin "74") (pinfunction "P2[1]/PWM1[2]/RXD1/PIPESTAT0_74") (pintype "bidirectional"))
    )
    (net (code "86") (name "unconnected-(U401-P2[4]{slash}PWM1[5]{slash}DSR1{slash}TRACESYNC-Pad69)") (class "Default")
      (node (ref "U401") (pin "69") (pinfunction "P2[4]/PWM1[5]/DSR1/TRACESYNC_69") (pintype "bidirectional"))
    )
    (net (code "87") (name "unconnected-(U401-P2[5]{slash}PWM1[6]{slash}DTR1{slash}TRACEPKT0-Pad68)") (class "Default")
      (node (ref "U401") (pin "68") (pinfunction "P2[5]/PWM1[6]/DTR1/TRACEPKT0_68") (pintype "bidirectional"))
    )
    (net (code "88") (name "unconnected-(U401-P2[6]{slash}PCAP1[0]{slash}RI1{slash}TRACEPKT1-Pad67)") (class "Default")
      (node (ref "U401") (pin "67") (pinfunction "P2[6]/PCAP1[0]/RI1/TRACEPKT1_67") (pintype "bidirectional"))
    )
    (net (code "89") (name "unconnected-(U401-P2[7]{slash}RD2{slash}RTS1{slash}TRACEPKT2-Pad66)") (class "Default")
      (node (ref "U401") (pin "66") (pinfunction "P2[7]/RD2/RTS1/TRACEPKT2_66") (pintype "bidirectional"))
    )
    (net (code "90") (name "unconnected-(U401-P2[8]{slash}TD2{slash}TXD2{slash}TRACEPKT3-Pad65)") (class "Default")
      (node (ref "U401") (pin "65") (pinfunction "P2[8]/TD2/TXD2/TRACEPKT3_65") (pintype "bidirectional"))
    )
    (net (code "91") (name "unconnected-(U401-P3[25]{slash}MAT0[0]{slash}PWM1[2]-Pad27)") (class "Default")
      (node (ref "U401") (pin "27") (pinfunction "P3[25]/MAT0[0]/PWM1[2]_27") (pintype "bidirectional"))
    )
    (net (code "92") (name "unconnected-(U401-P3[26]{slash}MAT0[1]{slash}PWM1[3]-Pad26)") (class "Default")
      (node (ref "U401") (pin "26") (pinfunction "P3[26]/MAT0[1]/PWM1[3]_26") (pintype "bidirectional"))
    )
    (net (code "93") (name "unconnected-(U401-P4[28]{slash}MAT2[0]{slash}TXD3-Pad82)") (class "Default")
      (node (ref "U401") (pin "82") (pinfunction "P4[28]/MAT2[0]/TXD3_82") (pintype "bidirectional"))
    )
    (net (code "94") (name "unconnected-(U401-P4[29]{slash}MAT2[1]{slash}RXD3-Pad85)") (class "Default")
      (node (ref "U401") (pin "85") (pinfunction "P4[29]/MAT2[1]/RXD3_85") (pintype "bidirectional"))
    )
    (net (code "95") (name "unconnected-(U401-RTCK-Pad100)") (class "Default")
      (node (ref "U401") (pin "100") (pinfunction "RTCK_100") (pintype "bidirectional"))
    )
    (net (code "96") (name "unconnected-(U401-RTCX1-Pad16)") (class "Default")
      (node (ref "U401") (pin "16") (pinfunction "RTCX1_16") (pintype "bidirectional"))
    )
    (net (code "97") (name "unconnected-(U401-RTCX2-Pad18)") (class "Default")
      (node (ref "U401") (pin "18") (pinfunction "RTCX2_18") (pintype "bidirectional"))
    )
    (net (code "98") (name "unconnected-(U401-TCK-Pad5)") (class "Default")
      (node (ref "U401") (pin "5") (pinfunction "TCK_5") (pintype "bidirectional"))
    )
    (net (code "99") (name "unconnected-(U401-TD0-Pad1)") (class "Default")
      (node (ref "U401") (pin "1") (pinfunction "TD0_1") (pintype "bidirectional"))
    )
    (net (code "100") (name "unconnected-(U401-TDI-Pad2)") (class "Default")
      (node (ref "U401") (pin "2") (pinfunction "TDI_2") (pintype "bidirectional"))
    )
    (net (code "101") (name "unconnected-(U401-TMS-Pad3)") (class "Default")
      (node (ref "U401") (pin "3") (pinfunction "TMS_3") (pintype "bidirectional"))
    )
    (net (code "102") (name "unconnected-(U501-CLKOUT-Pad22)") (class "Default")
      (node (ref "U501") (pin "22") (pinfunction "CLKOUT_22") (pintype "bidirectional"))
    )
    (net (code "103") (name "unconnected-(U501-ES_CL-Pad7)") (class "Default")
      (node (ref "U501") (pin "7") (pinfunction "ES_CL_7") (pintype "bidirectional"))
    )
    (net (code "104") (name "unconnected-(U501-ES_DA-Pad6)") (class "Default")
      (node (ref "U501") (pin "6") (pinfunction "ES_DA_6") (pintype "bidirectional"))
    )
  )
)
